# ElectronicCompass_T05.net
KiCad netlist of a schematic drawn in EAGLE
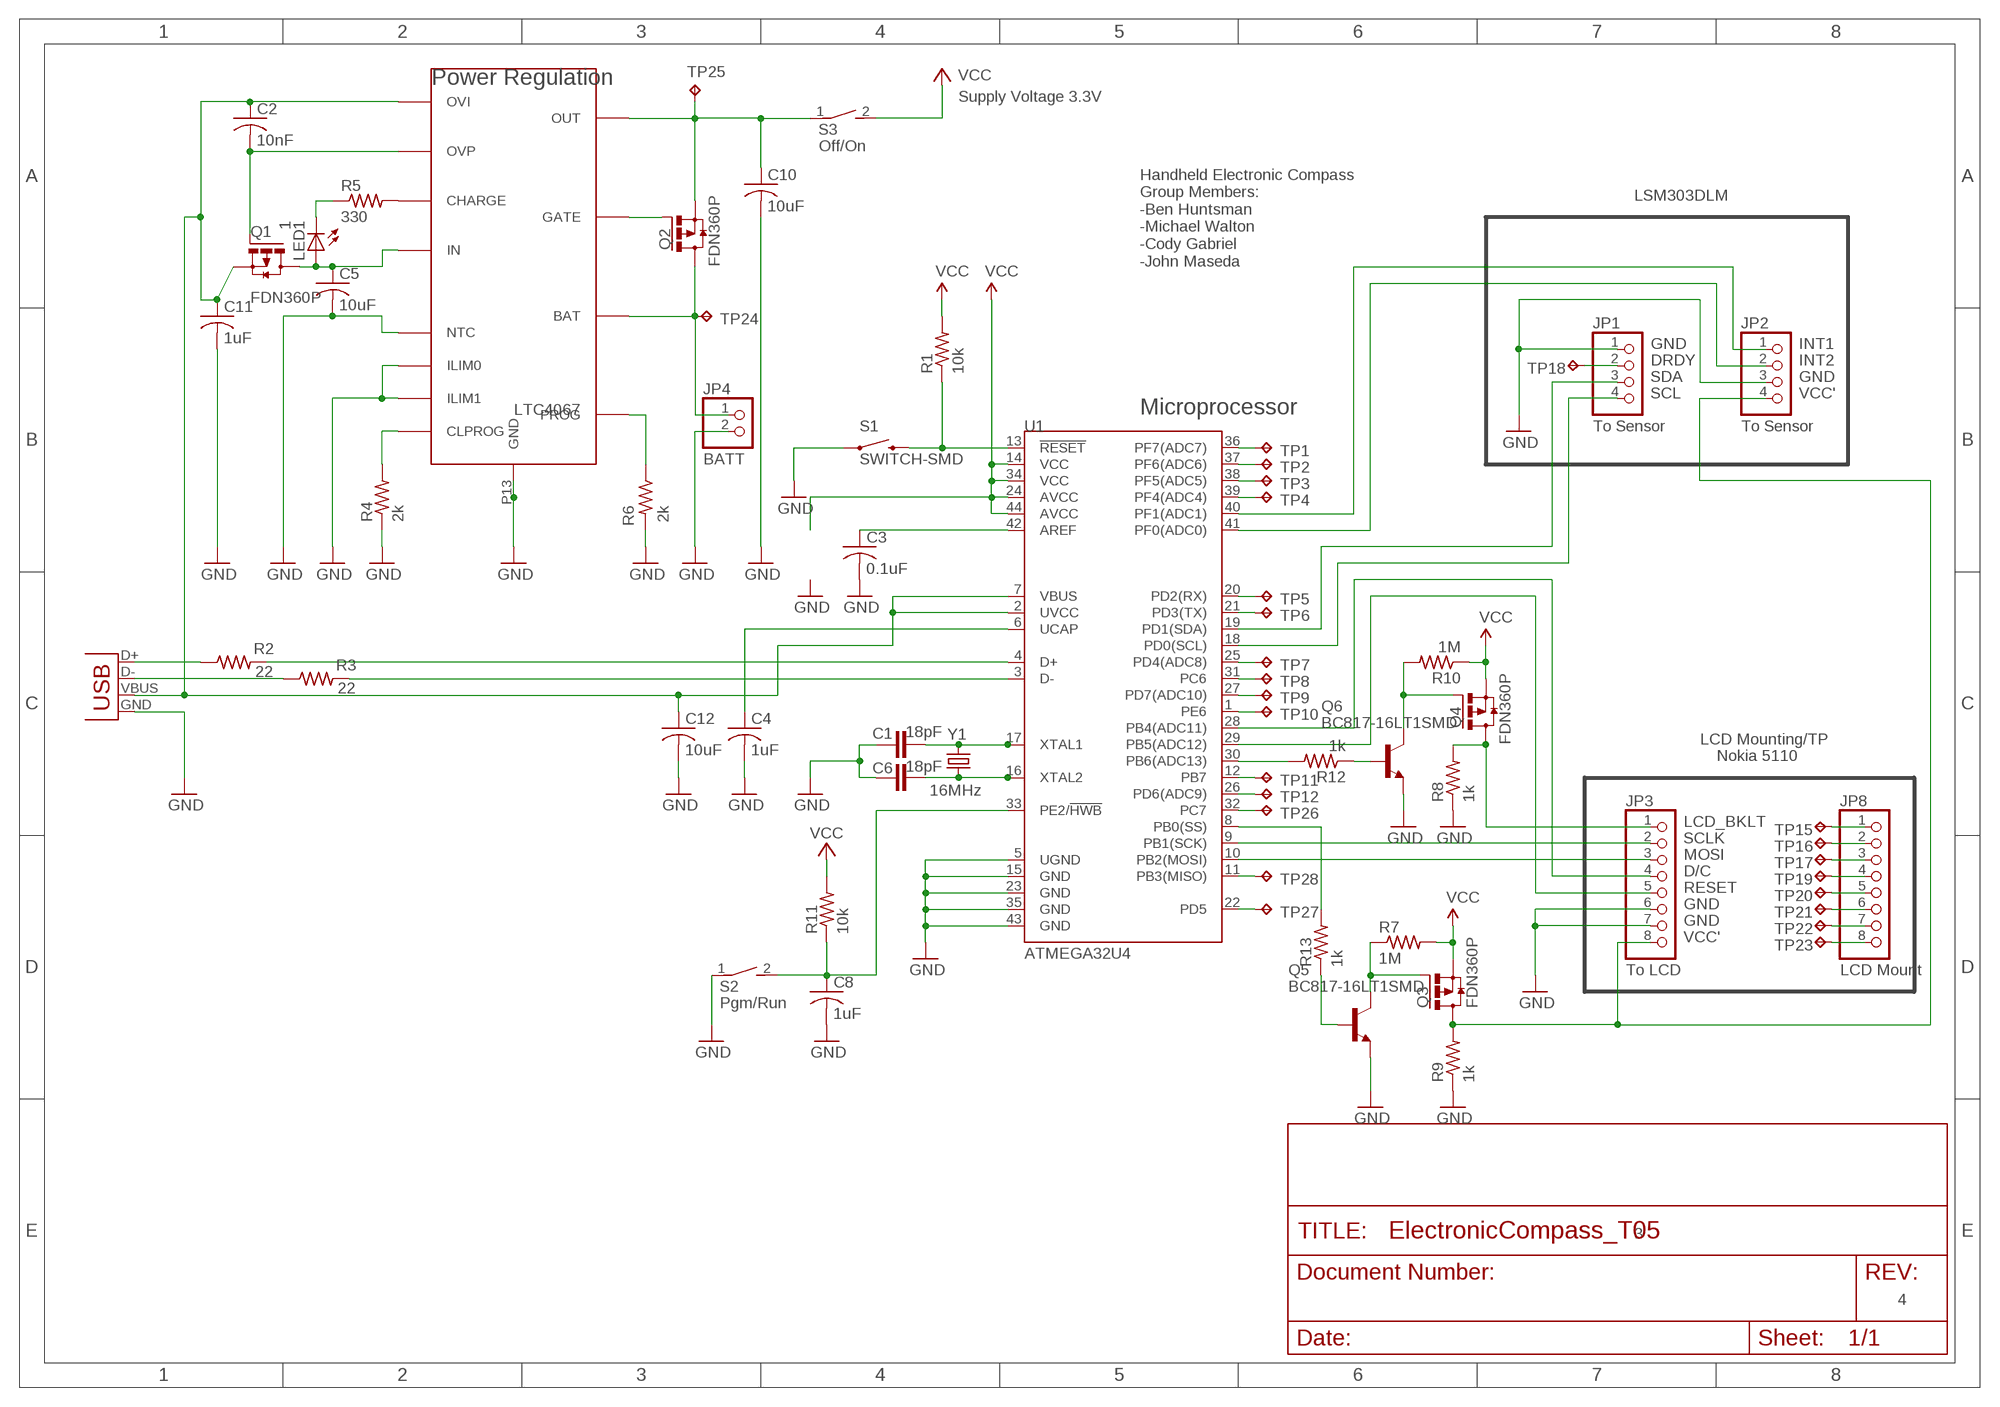
[diagram p0: schematic, sheet 1]

(export (version "E")
  (design (tool "Eeschema 10.0.6"))
  (components
    (comp (ref "C1")
      (value "18pF")
      (footprint "eagle-import:0402-CAP")
      (libsource (lib "eagle-import") (part "CAP0402-CAP"))
    )
    (comp (ref "C2")
      (value "10nF")
      (footprint "eagle-import:C0805")
      (libsource (lib "eagle-import") (part "C-USC0805"))
    )
    (comp (ref "C3")
      (value "0.1uF")
      (footprint "eagle-import:C0805")
      (libsource (lib "eagle-import") (part "C-USC0805"))
    )
    (comp (ref "C4")
      (value "1uF")
      (footprint "eagle-import:C0805")
      (libsource (lib "eagle-import") (part "C-USC0805"))
    )
    (comp (ref "C5")
      (value "10uF")
      (footprint "eagle-import:C0805")
      (libsource (lib "eagle-import") (part "C-USC0805"))
    )
    (comp (ref "C6")
      (value "18pF")
      (footprint "eagle-import:0402-CAP")
      (libsource (lib "eagle-import") (part "CAP0402-CAP"))
    )
    (comp (ref "C8")
      (value "1uF")
      (footprint "eagle-import:C0805")
      (libsource (lib "eagle-import") (part "C-USC0805"))
    )
    (comp (ref "C10")
      (value "10uF")
      (footprint "eagle-import:C0805")
      (libsource (lib "eagle-import") (part "C-USC0805"))
    )
    (comp (ref "C11")
      (value "1uF")
      (footprint "eagle-import:C0805")
      (libsource (lib "eagle-import") (part "C-USC0805"))
    )
    (comp (ref "C12")
      (value "10uF")
      (footprint "eagle-import:C0805")
      (libsource (lib "eagle-import") (part "C-USC0805"))
    )
    (comp (ref "JP1")
      (value "To Sensor")
      (footprint "eagle-import:1X04")
      (libsource (lib "eagle-import") (part "PINHD-1X4"))
    )
    (comp (ref "JP2")
      (value "To Sensor")
      (footprint "eagle-import:1X04")
      (libsource (lib "eagle-import") (part "PINHD-1X4"))
    )
    (comp (ref "JP3")
      (value "To LCD")
      (footprint "eagle-import:1X08")
      (libsource (lib "eagle-import") (part "PINHD-1X8"))
    )
    (comp (ref "JP4")
      (value "BATT")
      (footprint "eagle-import:1X02")
      (libsource (lib "eagle-import") (part "PINHD-1X2"))
    )
    (comp (ref "JP8")
      (value "LCD Mount")
      (footprint "eagle-import:1X08")
      (libsource (lib "eagle-import") (part "PINHD-1X8"))
    )
    (comp (ref "LED1")
      (value "1")
      (footprint "eagle-import:CHIPLED_0805")
      (libsource (lib "eagle-import") (part "LEDCHIPLED_0805"))
    )
    (comp (ref "Q1")
      (value "FDN360P")
      (footprint "eagle-import:SUPER-SOT3")
      (libsource (lib "eagle-import") (part "FDN360P"))
    )
    (comp (ref "Q2")
      (value "FDN360P")
      (footprint "eagle-import:SUPER-SOT3")
      (libsource (lib "eagle-import") (part "FDN360P"))
    )
    (comp (ref "Q3")
      (value "FDN360P")
      (footprint "eagle-import:SUPER-SOT3")
      (libsource (lib "eagle-import") (part "FDN360P"))
    )
    (comp (ref "Q4")
      (value "FDN360P")
      (footprint "eagle-import:SUPER-SOT3")
      (libsource (lib "eagle-import") (part "FDN360P"))
    )
    (comp (ref "Q5")
      (value "BC817-16LT1SMD")
      (footprint "eagle-import:SOT23-BEC")
      (libsource (lib "eagle-import") (part "BC817SMD-16LT1"))
    )
    (comp (ref "Q6")
      (value "BC817-16LT1SMD")
      (footprint "eagle-import:SOT23-BEC")
      (libsource (lib "eagle-import") (part "BC817SMD-16LT1"))
    )
    (comp (ref "R1")
      (value "10k")
      (footprint "eagle-import:M0805")
      (libsource (lib "eagle-import") (part "resistor_R-US_M0805"))
    )
    (comp (ref "R2")
      (value "22")
      (footprint "eagle-import:M0805")
      (libsource (lib "eagle-import") (part "resistor_R-US_M0805"))
    )
    (comp (ref "R3")
      (value "22")
      (footprint "eagle-import:M0805")
      (libsource (lib "eagle-import") (part "resistor_R-US_M0805"))
    )
    (comp (ref "R4")
      (value "2k")
      (footprint "eagle-import:M0805")
      (libsource (lib "eagle-import") (part "resistor_R-US_M0805"))
    )
    (comp (ref "R5")
      (value "330")
      (footprint "eagle-import:M0805")
      (libsource (lib "eagle-import") (part "resistor_R-US_M0805"))
    )
    (comp (ref "R6")
      (value "2k")
      (footprint "eagle-import:M0805")
      (libsource (lib "eagle-import") (part "resistor_R-US_M0805"))
    )
    (comp (ref "R7")
      (value "1M")
      (footprint "eagle-import:M0805")
      (libsource (lib "eagle-import") (part "resistor_R-US_M0805"))
    )
    (comp (ref "R8")
      (value "1k")
      (footprint "eagle-import:M0805")
      (libsource (lib "eagle-import") (part "R-US_M0805"))
    )
    (comp (ref "R9")
      (value "1k")
      (footprint "eagle-import:M0805")
      (libsource (lib "eagle-import") (part "resistor_R-US_M0805"))
    )
    (comp (ref "R10")
      (value "1M")
      (footprint "eagle-import:M0805")
      (libsource (lib "eagle-import") (part "resistor_R-US_M0805"))
    )
    (comp (ref "R11")
      (value "10k")
      (footprint "eagle-import:M0805")
      (libsource (lib "eagle-import") (part "resistor_R-US_M0805"))
    )
    (comp (ref "R12")
      (value "1k")
      (footprint "eagle-import:M0805")
      (libsource (lib "eagle-import") (part "R-US_M0805"))
    )
    (comp (ref "R13")
      (value "1k")
      (footprint "eagle-import:M0805")
      (libsource (lib "eagle-import") (part "resistor_R-US_M0805"))
    )
    (comp (ref "S1")
      (value "SWITCH-SMD")
      (footprint "eagle-import:TACTILE_SWITCH_SMD")
      (libsource (lib "eagle-import") (part "SWITCH-MOMENTARY-2SMD"))
    )
    (comp (ref "S2")
      (value "Pgm/Run")
      (footprint "eagle-import:DS-01")
      (libsource (lib "eagle-import") (part "DS01E"))
    )
    (comp (ref "S3")
      (value "Off/On")
      (footprint "eagle-import:DS-01")
      (libsource (lib "eagle-import") (part "DS01E"))
    )
    (comp (ref "TP1")
      (value "TPTP06R")
      (footprint "eagle-import:TP06R")
      (libsource (lib "eagle-import") (part "TPTP06R"))
    )
    (comp (ref "TP2")
      (value "TPTP06R")
      (footprint "eagle-import:TP06R")
      (libsource (lib "eagle-import") (part "TPTP06R"))
    )
    (comp (ref "TP3")
      (value "TPTP06R")
      (footprint "eagle-import:TP06R")
      (libsource (lib "eagle-import") (part "TPTP06R"))
    )
    (comp (ref "TP4")
      (value "TPTP06R")
      (footprint "eagle-import:TP06R")
      (libsource (lib "eagle-import") (part "TPTP06R"))
    )
    (comp (ref "TP5")
      (value "TPTP06R")
      (footprint "eagle-import:TP06R")
      (libsource (lib "eagle-import") (part "TPTP06R"))
    )
    (comp (ref "TP6")
      (value "TPTP06R")
      (footprint "eagle-import:TP06R")
      (libsource (lib "eagle-import") (part "TPTP06R"))
    )
    (comp (ref "TP7")
      (value "TPTP06R")
      (footprint "eagle-import:TP06R")
      (libsource (lib "eagle-import") (part "TPTP06R"))
    )
    (comp (ref "TP8")
      (value "TPTP06R")
      (footprint "eagle-import:TP06R")
      (libsource (lib "eagle-import") (part "TPTP06R"))
    )
    (comp (ref "TP9")
      (value "TPTP06R")
      (footprint "eagle-import:TP06R")
      (libsource (lib "eagle-import") (part "TPTP06R"))
    )
    (comp (ref "TP10")
      (value "TPTP06R")
      (footprint "eagle-import:TP06R")
      (libsource (lib "eagle-import") (part "TPTP06R"))
    )
    (comp (ref "TP11")
      (value "TPTP06R")
      (footprint "eagle-import:TP06R")
      (libsource (lib "eagle-import") (part "TPTP06R"))
    )
    (comp (ref "TP12")
      (value "TPTP06R")
      (footprint "eagle-import:TP06R")
      (libsource (lib "eagle-import") (part "TPTP06R"))
    )
    (comp (ref "TP15")
      (value "TPTP06R")
      (footprint "eagle-import:TP06R")
      (libsource (lib "eagle-import") (part "TPTP06R"))
    )
    (comp (ref "TP16")
      (value "TPTP06R")
      (footprint "eagle-import:TP06R")
      (libsource (lib "eagle-import") (part "TPTP06R"))
    )
    (comp (ref "TP17")
      (value "TPTP06R")
      (footprint "eagle-import:TP06R")
      (libsource (lib "eagle-import") (part "TPTP06R"))
    )
    (comp (ref "TP18")
      (value "TPTP06R")
      (footprint "eagle-import:TP06R")
      (libsource (lib "eagle-import") (part "TPTP06R"))
    )
    (comp (ref "TP19")
      (value "TPTP06R")
      (footprint "eagle-import:TP06R")
      (libsource (lib "eagle-import") (part "TPTP06R"))
    )
    (comp (ref "TP20")
      (value "TPTP06R")
      (footprint "eagle-import:TP06R")
      (libsource (lib "eagle-import") (part "TPTP06R"))
    )
    (comp (ref "TP21")
      (value "TPTP06R")
      (footprint "eagle-import:TP06R")
      (libsource (lib "eagle-import") (part "TPTP06R"))
    )
    (comp (ref "TP22")
      (value "TPTP06R")
      (footprint "eagle-import:TP06R")
      (libsource (lib "eagle-import") (part "TPTP06R"))
    )
    (comp (ref "TP23")
      (value "TPTP06R")
      (footprint "eagle-import:TP06R")
      (libsource (lib "eagle-import") (part "TPTP06R"))
    )
    (comp (ref "TP24")
      (value "TPTP06R")
      (footprint "eagle-import:TP06R")
      (libsource (lib "eagle-import") (part "TPTP06R"))
    )
    (comp (ref "TP25")
      (value "TPTP06R")
      (footprint "eagle-import:TP06R")
      (libsource (lib "eagle-import") (part "TPTP06R"))
    )
    (comp (ref "TP26")
      (value "TPTP06R")
      (footprint "eagle-import:TP06R")
      (libsource (lib "eagle-import") (part "TPTP06R"))
    )
    (comp (ref "TP27")
      (value "TPTP06R")
      (footprint "eagle-import:TP06R")
      (libsource (lib "eagle-import") (part "TPTP06R"))
    )
    (comp (ref "TP28")
      (value "TPTP06R")
      (footprint "eagle-import:TP06R")
      (libsource (lib "eagle-import") (part "TPTP06R"))
    )
    (comp (ref "U1")
      (value "ATMEGA32U4")
      (footprint "eagle-import:QFN-44-NOPAD")
      (libsource (lib "eagle-import") (part "ATMEGA32U4QFN2"))
    )
    (comp (ref "U2")
      (value "LTC4067")
      (footprint "eagle-import:DFN-12")
      (libsource (lib "eagle-import") (part "LTC4067"))
    )
    (comp (ref "X1")
      (value "USBSMD")
      (footprint "eagle-import:USB-MINIB")
      (libsource (lib "eagle-import") (part "USBSMD"))
    )
    (comp (ref "Y1")
      (value "16MHz")
      (footprint "eagle-import:CRYSTAL-SMD-5X3")
      (libsource (lib "eagle-import") (part "CRYSTAL5X3"))
    )
  )
  (nets
    (net (code "1") (name "/DRDY") (class "Default")
      (node (ref "JP1") (pin "2") (pinfunction "2_2") (pintype "passive"))
      (node (ref "TP18") (pin "TP") (pinfunction "TP_TP") (pintype "input"))
    )
    (net (code "2") (name "/D{slash}C") (class "Default")
      (node (ref "JP3") (pin "4") (pinfunction "4_4") (pintype "passive"))
      (node (ref "U1") (pin "28") (pinfunction "PB4(ADC11)_28") (pintype "bidirectional"))
    )
    (net (code "3") (name "/INT1") (class "Default")
      (node (ref "JP2") (pin "1") (pinfunction "1_1") (pintype "passive"))
      (node (ref "U1") (pin "40") (pinfunction "PF1(ADC1)_40") (pintype "bidirectional"))
    )
    (net (code "4") (name "/INT2") (class "Default")
      (node (ref "JP2") (pin "2") (pinfunction "2_2") (pintype "passive"))
      (node (ref "U1") (pin "41") (pinfunction "PF0(ADC0)_41") (pintype "bidirectional"))
    )
    (net (code "5") (name "/LCD_BKLT") (class "Default")
      (node (ref "JP3") (pin "1") (pinfunction "1_1") (pintype "passive"))
      (node (ref "Q4") (pin "3") (pinfunction "D_3") (pintype "passive"))
      (node (ref "R8") (pin "2") (pinfunction "2_2") (pintype "passive"))
    )
    (net (code "6") (name "/MOSI") (class "Default")
      (node (ref "JP3") (pin "3") (pinfunction "3_3") (pintype "passive"))
      (node (ref "U1") (pin "10") (pinfunction "PB2(MOSI)_10") (pintype "bidirectional"))
    )
    (net (code "7") (name "/RESET") (class "Default")
      (node (ref "JP3") (pin "5") (pinfunction "5_5") (pintype "passive"))
      (node (ref "U1") (pin "29") (pinfunction "PB5(ADC12)_29") (pintype "bidirectional"))
    )
    (net (code "8") (name "/SCL") (class "Default")
      (node (ref "JP1") (pin "4") (pinfunction "4_4") (pintype "passive"))
      (node (ref "U1") (pin "18") (pinfunction "PD0(SCL)_18") (pintype "bidirectional"))
    )
    (net (code "9") (name "/SCLK") (class "Default")
      (node (ref "JP3") (pin "2") (pinfunction "2_2") (pintype "passive"))
      (node (ref "U1") (pin "9") (pinfunction "PB1(SCK)_9") (pintype "bidirectional"))
    )
    (net (code "10") (name "/SDA") (class "Default")
      (node (ref "JP1") (pin "3") (pinfunction "3_3") (pintype "passive"))
      (node (ref "U1") (pin "19") (pinfunction "PD1(SDA)_19") (pintype "bidirectional"))
    )
    (net (code "11") (name "/VCC'") (class "Default")
      (node (ref "JP2") (pin "4") (pinfunction "4_4") (pintype "passive"))
      (node (ref "JP3") (pin "8") (pinfunction "8_8") (pintype "passive"))
      (node (ref "Q3") (pin "3") (pinfunction "D_3") (pintype "passive"))
      (node (ref "R9") (pin "2") (pinfunction "2_2") (pintype "passive"))
    )
    (net (code "12") (name "GND") (class "Default")
      (node (ref "C1") (pin "1") (pinfunction "1_1") (pintype "passive"))
      (node (ref "C10") (pin "2") (pinfunction "2_2") (pintype "passive"))
      (node (ref "C11") (pin "2") (pinfunction "2_2") (pintype "passive"))
      (node (ref "C12") (pin "2") (pinfunction "2_2") (pintype "passive"))
      (node (ref "C3") (pin "2") (pinfunction "2_2") (pintype "passive"))
      (node (ref "C4") (pin "2") (pinfunction "2_2") (pintype "passive"))
      (node (ref "C5") (pin "2") (pinfunction "2_2") (pintype "passive"))
      (node (ref "C6") (pin "1") (pinfunction "1_1") (pintype "passive"))
      (node (ref "C8") (pin "2") (pinfunction "2_2") (pintype "passive"))
      (node (ref "JP1") (pin "1") (pinfunction "1_1") (pintype "passive"))
      (node (ref "JP2") (pin "3") (pinfunction "3_3") (pintype "passive"))
      (node (ref "JP3") (pin "6") (pinfunction "6_6") (pintype "passive"))
      (node (ref "JP3") (pin "7") (pinfunction "7_7") (pintype "passive"))
      (node (ref "JP4") (pin "2") (pinfunction "2_2") (pintype "passive"))
      (node (ref "Q5") (pin "E") (pinfunction "E_E") (pintype "passive"))
      (node (ref "Q6") (pin "E") (pinfunction "E_E") (pintype "passive"))
      (node (ref "R4") (pin "1") (pinfunction "1_1") (pintype "passive"))
      (node (ref "R6") (pin "2") (pinfunction "2_2") (pintype "passive"))
      (node (ref "R8") (pin "1") (pinfunction "1_1") (pintype "passive"))
      (node (ref "R9") (pin "1") (pinfunction "1_1") (pintype "passive"))
      (node (ref "S1") (pin "1") (pinfunction "1_1") (pintype "passive"))
      (node (ref "S2") (pin "1") (pinfunction "1_1") (pintype "passive"))
      (node (ref "U1") (pin "15") (pinfunction "GND_15") (pintype "bidirectional"))
      (node (ref "U1") (pin "23") (pinfunction "GND_23") (pintype "bidirectional"))
      (node (ref "U1") (pin "35") (pinfunction "GND_35") (pintype "bidirectional"))
      (node (ref "U1") (pin "43") (pinfunction "GND_43") (pintype "bidirectional"))
      (node (ref "U1") (pin "5") (pinfunction "UGND_5") (pintype "bidirectional"))
      (node (ref "U2") (pin "P13") (pinfunction "GND_P13") (pintype "bidirectional"))
      (node (ref "U2") (pin "P3") (pinfunction "NTC_P3") (pintype "bidirectional"))
      (node (ref "U2") (pin "P4") (pinfunction "ILIM0_P4") (pintype "bidirectional"))
      (node (ref "U2") (pin "P5") (pinfunction "ILIM1_P5") (pintype "bidirectional"))
      (node (ref "X1") (pin "GND") (pinfunction "GND_GND") (pintype "bidirectional"))
    )
    (net (code "13") (name "Net-(JP8-Pad1)") (class "Default")
      (node (ref "JP8") (pin "1") (pinfunction "1_1") (pintype "passive"))
      (node (ref "TP15") (pin "TP") (pinfunction "TP_TP") (pintype "input"))
    )
    (net (code "14") (name "Net-(JP8-Pad2)") (class "Default")
      (node (ref "JP8") (pin "2") (pinfunction "2_2") (pintype "passive"))
      (node (ref "TP16") (pin "TP") (pinfunction "TP_TP") (pintype "input"))
    )
    (net (code "15") (name "Net-(JP8-Pad3)") (class "Default")
      (node (ref "JP8") (pin "3") (pinfunction "3_3") (pintype "passive"))
      (node (ref "TP17") (pin "TP") (pinfunction "TP_TP") (pintype "input"))
    )
    (net (code "16") (name "Net-(JP8-Pad4)") (class "Default")
      (node (ref "JP8") (pin "4") (pinfunction "4_4") (pintype "passive"))
      (node (ref "TP19") (pin "TP") (pinfunction "TP_TP") (pintype "input"))
    )
    (net (code "17") (name "Net-(JP8-Pad5)") (class "Default")
      (node (ref "JP8") (pin "5") (pinfunction "5_5") (pintype "passive"))
      (node (ref "TP20") (pin "TP") (pinfunction "TP_TP") (pintype "input"))
    )
    (net (code "18") (name "Net-(JP8-Pad6)") (class "Default")
      (node (ref "JP8") (pin "6") (pinfunction "6_6") (pintype "passive"))
      (node (ref "TP21") (pin "TP") (pinfunction "TP_TP") (pintype "input"))
    )
    (net (code "19") (name "Net-(JP8-Pad7)") (class "Default")
      (node (ref "JP8") (pin "7") (pinfunction "7_7") (pintype "passive"))
      (node (ref "TP22") (pin "TP") (pinfunction "TP_TP") (pintype "input"))
    )
    (net (code "20") (name "Net-(JP8-Pad8)") (class "Default")
      (node (ref "JP8") (pin "8") (pinfunction "8_8") (pintype "passive"))
      (node (ref "TP23") (pin "TP") (pinfunction "TP_TP") (pintype "input"))
    )
    (net (code "21") (name "Net-(LED1-PadC)") (class "Default")
      (node (ref "LED1") (pin "C") (pinfunction "C_C") (pintype "passive"))
      (node (ref "R5") (pin "1") (pinfunction "1_1") (pintype "passive"))
    )
    (net (code "22") (name "Net-(Q1-D)") (class "Default")
      (node (ref "C5") (pin "1") (pinfunction "1_1") (pintype "passive"))
      (node (ref "LED1") (pin "A") (pinfunction "A_A") (pintype "passive"))
      (node (ref "Q1") (pin "3") (pinfunction "D_3") (pintype "passive"))
      (node (ref "U2") (pin "P12") (pinfunction "IN_P12") (pintype "bidirectional"))
    )
    (net (code "23") (name "Net-(Q1-G)") (class "Default")
      (node (ref "C2") (pin "2") (pinfunction "2_2") (pintype "passive"))
      (node (ref "Q1") (pin "1") (pinfunction "G_1") (pintype "passive"))
      (node (ref "U2") (pin "P7") (pinfunction "OVP_P7") (pintype "bidirectional"))
    )
    (net (code "24") (name "Net-(Q1-S)") (class "Default")
      (node (ref "C11") (pin "1") (pinfunction "1_1") (pintype "passive"))
      (node (ref "C12") (pin "1") (pinfunction "1_1") (pintype "passive"))
      (node (ref "C2") (pin "1") (pinfunction "1_1") (pintype "passive"))
      (node (ref "Q1") (pin "2") (pinfunction "S_2") (pintype "passive"))
      (node (ref "U1") (pin "2") (pinfunction "UVCC_2") (pintype "bidirectional"))
      (node (ref "U1") (pin "7") (pinfunction "VBUS_7") (pintype "bidirectional"))
      (node (ref "U2") (pin "P6") (pinfunction "OVI_P6") (pintype "bidirectional"))
      (node (ref "X1") (pin "VBUS") (pinfunction "VBUS_VBUS") (pintype "bidirectional"))
    )
    (net (code "25") (name "Net-(Q2-D)") (class "Default")
      (node (ref "JP4") (pin "1") (pinfunction "1_1") (pintype "passive"))
      (node (ref "Q2") (pin "3") (pinfunction "D_3") (pintype "passive"))
      (node (ref "TP24") (pin "TP") (pinfunction "TP_TP") (pintype "input"))
      (node (ref "U2") (pin "P10") (pinfunction "BAT_P10") (pintype "bidirectional"))
    )
    (net (code "26") (name "Net-(Q2-G)") (class "Default")
      (node (ref "Q2") (pin "1") (pinfunction "G_1") (pintype "passive"))
      (node (ref "U2") (pin "P9") (pinfunction "GATE_P9") (pintype "bidirectional"))
    )
    (net (code "27") (name "Net-(Q2-S)") (class "Default")
      (node (ref "C10") (pin "1") (pinfunction "1_1") (pintype "passive"))
      (node (ref "Q2") (pin "2") (pinfunction "S_2") (pintype "passive"))
      (node (ref "S3") (pin "1") (pinfunction "1_1") (pintype "passive"))
      (node (ref "TP25") (pin "TP") (pinfunction "TP_TP") (pintype "input"))
      (node (ref "U2") (pin "P11") (pinfunction "OUT_P11") (pintype "bidirectional"))
    )
    (net (code "28") (name "Net-(Q3-G)") (class "Default")
      (node (ref "Q3") (pin "1") (pinfunction "G_1") (pintype "passive"))
      (node (ref "Q5") (pin "C") (pinfunction "C_C") (pintype "passive"))
      (node (ref "R7") (pin "1") (pinfunction "1_1") (pintype "passive"))
    )
    (net (code "29") (name "Net-(Q4-G)") (class "Default")
      (node (ref "Q4") (pin "1") (pinfunction "G_1") (pintype "passive"))
      (node (ref "Q6") (pin "C") (pinfunction "C_C") (pintype "passive"))
      (node (ref "R10") (pin "2") (pinfunction "2_2") (pintype "passive"))
    )
    (net (code "30") (name "Net-(Q5-PadB)") (class "Default")
      (node (ref "Q5") (pin "B") (pinfunction "B_B") (pintype "passive"))
      (node (ref "R13") (pin "1") (pinfunction "1_1") (pintype "passive"))
    )
    (net (code "31") (name "Net-(Q6-PadB)") (class "Default")
      (node (ref "Q6") (pin "B") (pinfunction "B_B") (pintype "passive"))
      (node (ref "R12") (pin "1") (pinfunction "1_1") (pintype "passive"))
    )
    (net (code "32") (name "Net-(R2-Pad1)") (class "Default")
      (node (ref "R2") (pin "1") (pinfunction "1_1") (pintype "passive"))
      (node (ref "X1") (pin "D+") (pinfunction "D+_D+") (pintype "bidirectional"))
    )
    (net (code "33") (name "Net-(R3-Pad1)") (class "Default")
      (node (ref "R3") (pin "1") (pinfunction "1_1") (pintype "passive"))
      (node (ref "X1") (pin "D-") (pinfunction "D-_D-") (pintype "bidirectional"))
    )
    (net (code "34") (name "Net-(S1-2)") (class "Default")
      (node (ref "R1") (pin "1") (pinfunction "1_1") (pintype "passive"))
      (node (ref "S1") (pin "3") (pinfunction "2_3") (pintype "passive"))
      (node (ref "U1") (pin "13") (pinfunction "~{RESET}_13") (pintype "bidirectional"))
    )
    (net (code "35") (name "Net-(U1-AREF)") (class "Default")
      (node (ref "C3") (pin "1") (pinfunction "1_1") (pintype "passive"))
      (node (ref "U1") (pin "42") (pinfunction "AREF_42") (pintype "bidirectional"))
    )
    (net (code "36") (name "Net-(U1-D+)") (class "Default")
      (node (ref "R2") (pin "2") (pinfunction "2_2") (pintype "passive"))
      (node (ref "U1") (pin "4") (pinfunction "D+_4") (pintype "bidirectional"))
    )
    (net (code "37") (name "Net-(U1-D-)") (class "Default")
      (node (ref "R3") (pin "2") (pinfunction "2_2") (pintype "passive"))
      (node (ref "U1") (pin "3") (pinfunction "D-_3") (pintype "bidirectional"))
    )
    (net (code "38") (name "Net-(U1-PB0(SS))") (class "Default")
      (node (ref "R13") (pin "2") (pinfunction "2_2") (pintype "passive"))
      (node (ref "U1") (pin "8") (pinfunction "PB0(SS)_8") (pintype "bidirectional"))
    )
    (net (code "39") (name "Net-(U1-PB3(MISO))") (class "Default")
      (node (ref "TP28") (pin "TP") (pinfunction "TP_TP") (pintype "input"))
      (node (ref "U1") (pin "11") (pinfunction "PB3(MISO)_11") (pintype "bidirectional"))
    )
    (net (code "40") (name "Net-(U1-PB6(ADC13))") (class "Default")
      (node (ref "R12") (pin "2") (pinfunction "2_2") (pintype "passive"))
      (node (ref "U1") (pin "30") (pinfunction "PB6(ADC13)_30") (pintype "bidirectional"))
    )
    (net (code "41") (name "Net-(U1-PB7)") (class "Default")
      (node (ref "TP11") (pin "TP") (pinfunction "TP_TP") (pintype "input"))
      (node (ref "U1") (pin "12") (pinfunction "PB7_12") (pintype "bidirectional"))
    )
    (net (code "42") (name "Net-(U1-PC6)") (class "Default")
      (node (ref "TP8") (pin "TP") (pinfunction "TP_TP") (pintype "input"))
      (node (ref "U1") (pin "31") (pinfunction "PC6_31") (pintype "bidirectional"))
    )
    (net (code "43") (name "Net-(U1-PC7)") (class "Default")
      (node (ref "TP26") (pin "TP") (pinfunction "TP_TP") (pintype "input"))
      (node (ref "U1") (pin "32") (pinfunction "PC7_32") (pintype "bidirectional"))
    )
    (net (code "44") (name "Net-(U1-PD2(RX))") (class "Default")
      (node (ref "TP5") (pin "TP") (pinfunction "TP_TP") (pintype "input"))
      (node (ref "U1") (pin "20") (pinfunction "PD2(RX)_20") (pintype "bidirectional"))
    )
    (net (code "45") (name "Net-(U1-PD3(TX))") (class "Default")
      (node (ref "TP6") (pin "TP") (pinfunction "TP_TP") (pintype "input"))
      (node (ref "U1") (pin "21") (pinfunction "PD3(TX)_21") (pintype "bidirectional"))
    )
    (net (code "46") (name "Net-(U1-PD4(ADC8))") (class "Default")
      (node (ref "TP7") (pin "TP") (pinfunction "TP_TP") (pintype "input"))
      (node (ref "U1") (pin "25") (pinfunction "PD4(ADC8)_25") (pintype "bidirectional"))
    )
    (net (code "47") (name "Net-(U1-PD5)") (class "Default")
      (node (ref "TP27") (pin "TP") (pinfunction "TP_TP") (pintype "input"))
      (node (ref "U1") (pin "22") (pinfunction "PD5_22") (pintype "bidirectional"))
    )
    (net (code "48") (name "Net-(U1-PD6(ADC9))") (class "Default")
      (node (ref "TP12") (pin "TP") (pinfunction "TP_TP") (pintype "input"))
      (node (ref "U1") (pin "26") (pinfunction "PD6(ADC9)_26") (pintype "bidirectional"))
    )
    (net (code "49") (name "Net-(U1-PD7(ADC10))") (class "Default")
      (node (ref "TP9") (pin "TP") (pinfunction "TP_TP") (pintype "input"))
      (node (ref "U1") (pin "27") (pinfunction "PD7(ADC10)_27") (pintype "bidirectional"))
    )
    (net (code "50") (name "Net-(U1-PE2{slash}~{HWB})") (class "Default")
      (node (ref "C8") (pin "1") (pinfunction "1_1") (pintype "passive"))
      (node (ref "R11") (pin "1") (pinfunction "1_1") (pintype "passive"))
      (node (ref "S2") (pin "2") (pinfunction "2_2") (pintype "passive"))
      (node (ref "U1") (pin "33") (pinfunction "PE2/~{HWB}_33") (pintype "bidirectional"))
    )
    (net (code "51") (name "Net-(U1-PE6)") (class "Default")
      (node (ref "TP10") (pin "TP") (pinfunction "TP_TP") (pintype "input"))
      (node (ref "U1") (pin "1") (pinfunction "PE6_1") (pintype "bidirectional"))
    )
    (net (code "52") (name "Net-(U1-PF4(ADC4))") (class "Default")
      (node (ref "TP4") (pin "TP") (pinfunction "TP_TP") (pintype "input"))
      (node (ref "U1") (pin "39") (pinfunction "PF4(ADC4)_39") (pintype "bidirectional"))
    )
    (net (code "53") (name "Net-(U1-PF5(ADC5))") (class "Default")
      (node (ref "TP3") (pin "TP") (pinfunction "TP_TP") (pintype "input"))
      (node (ref "U1") (pin "38") (pinfunction "PF5(ADC5)_38") (pintype "bidirectional"))
    )
    (net (code "54") (name "Net-(U1-PF6(ADC6))") (class "Default")
      (node (ref "TP2") (pin "TP") (pinfunction "TP_TP") (pintype "input"))
      (node (ref "U1") (pin "37") (pinfunction "PF6(ADC6)_37") (pintype "bidirectional"))
    )
    (net (code "55") (name "Net-(U1-PF7(ADC7))") (class "Default")
      (node (ref "TP1") (pin "TP") (pinfunction "TP_TP") (pintype "input"))
      (node (ref "U1") (pin "36") (pinfunction "PF7(ADC7)_36") (pintype "bidirectional"))
    )
    (net (code "56") (name "Net-(U1-UCAP)") (class "Default")
      (node (ref "C4") (pin "1") (pinfunction "1_1") (pintype "passive"))
      (node (ref "U1") (pin "6") (pinfunction "UCAP_6") (pintype "bidirectional"))
    )
    (net (code "57") (name "Net-(U1-XTAL1)") (class "Default")
      (node (ref "C1") (pin "2") (pinfunction "2_2") (pintype "passive"))
      (node (ref "U1") (pin "17") (pinfunction "XTAL1_17") (pintype "bidirectional"))
      (node (ref "Y1") (pin "3") (pinfunction "2_3") (pintype "passive"))
    )
    (net (code "58") (name "Net-(U1-XTAL2)") (class "Default")
      (node (ref "C6") (pin "2") (pinfunction "2_2") (pintype "passive"))
      (node (ref "U1") (pin "16") (pinfunction "XTAL2_16") (pintype "bidirectional"))
      (node (ref "Y1") (pin "1") (pinfunction "1_1") (pintype "passive"))
    )
    (net (code "59") (name "Net-(U2-CHARGE)") (class "Default")
      (node (ref "R5") (pin "2") (pinfunction "2_2") (pintype "passive"))
      (node (ref "U2") (pin "P2") (pinfunction "CHARGE_P2") (pintype "bidirectional"))
    )
    (net (code "60") (name "Net-(U2-CLPROG)") (class "Default")
      (node (ref "R4") (pin "2") (pinfunction "2_2") (pintype "passive"))
      (node (ref "U2") (pin "P1") (pinfunction "CLPROG_P1") (pintype "bidirectional"))
    )
    (net (code "61") (name "Net-(U2-PROG)") (class "Default")
      (node (ref "R6") (pin "1") (pinfunction "1_1") (pintype "passive"))
      (node (ref "U2") (pin "P8") (pinfunction "PROG_P8") (pintype "bidirectional"))
    )
    (net (code "62") (name "VCC") (class "Default")
      (node (ref "Q3") (pin "2") (pinfunction "S_2") (pintype "passive"))
      (node (ref "Q4") (pin "2") (pinfunction "S_2") (pintype "passive"))
      (node (ref "R1") (pin "2") (pinfunction "2_2") (pintype "passive"))
      (node (ref "R10") (pin "1") (pinfunction "1_1") (pintype "passive"))
      (node (ref "R11") (pin "2") (pinfunction "2_2") (pintype "passive"))
      (node (ref "R7") (pin "2") (pinfunction "2_2") (pintype "passive"))
      (node (ref "S3") (pin "2") (pinfunction "2_2") (pintype "passive"))
      (node (ref "U1") (pin "14") (pinfunction "VCC_14") (pintype "bidirectional"))
      (node (ref "U1") (pin "24") (pinfunction "AVCC_24") (pintype "bidirectional"))
      (node (ref "U1") (pin "34") (pinfunction "VCC_34") (pintype "bidirectional"))
      (node (ref "U1") (pin "44") (pinfunction "AVCC_44") (pintype "bidirectional"))
    )
  )
)
